# BaseMachine_Sequencer_UI.net
KiCad netlist of a schematic drawn in EAGLE
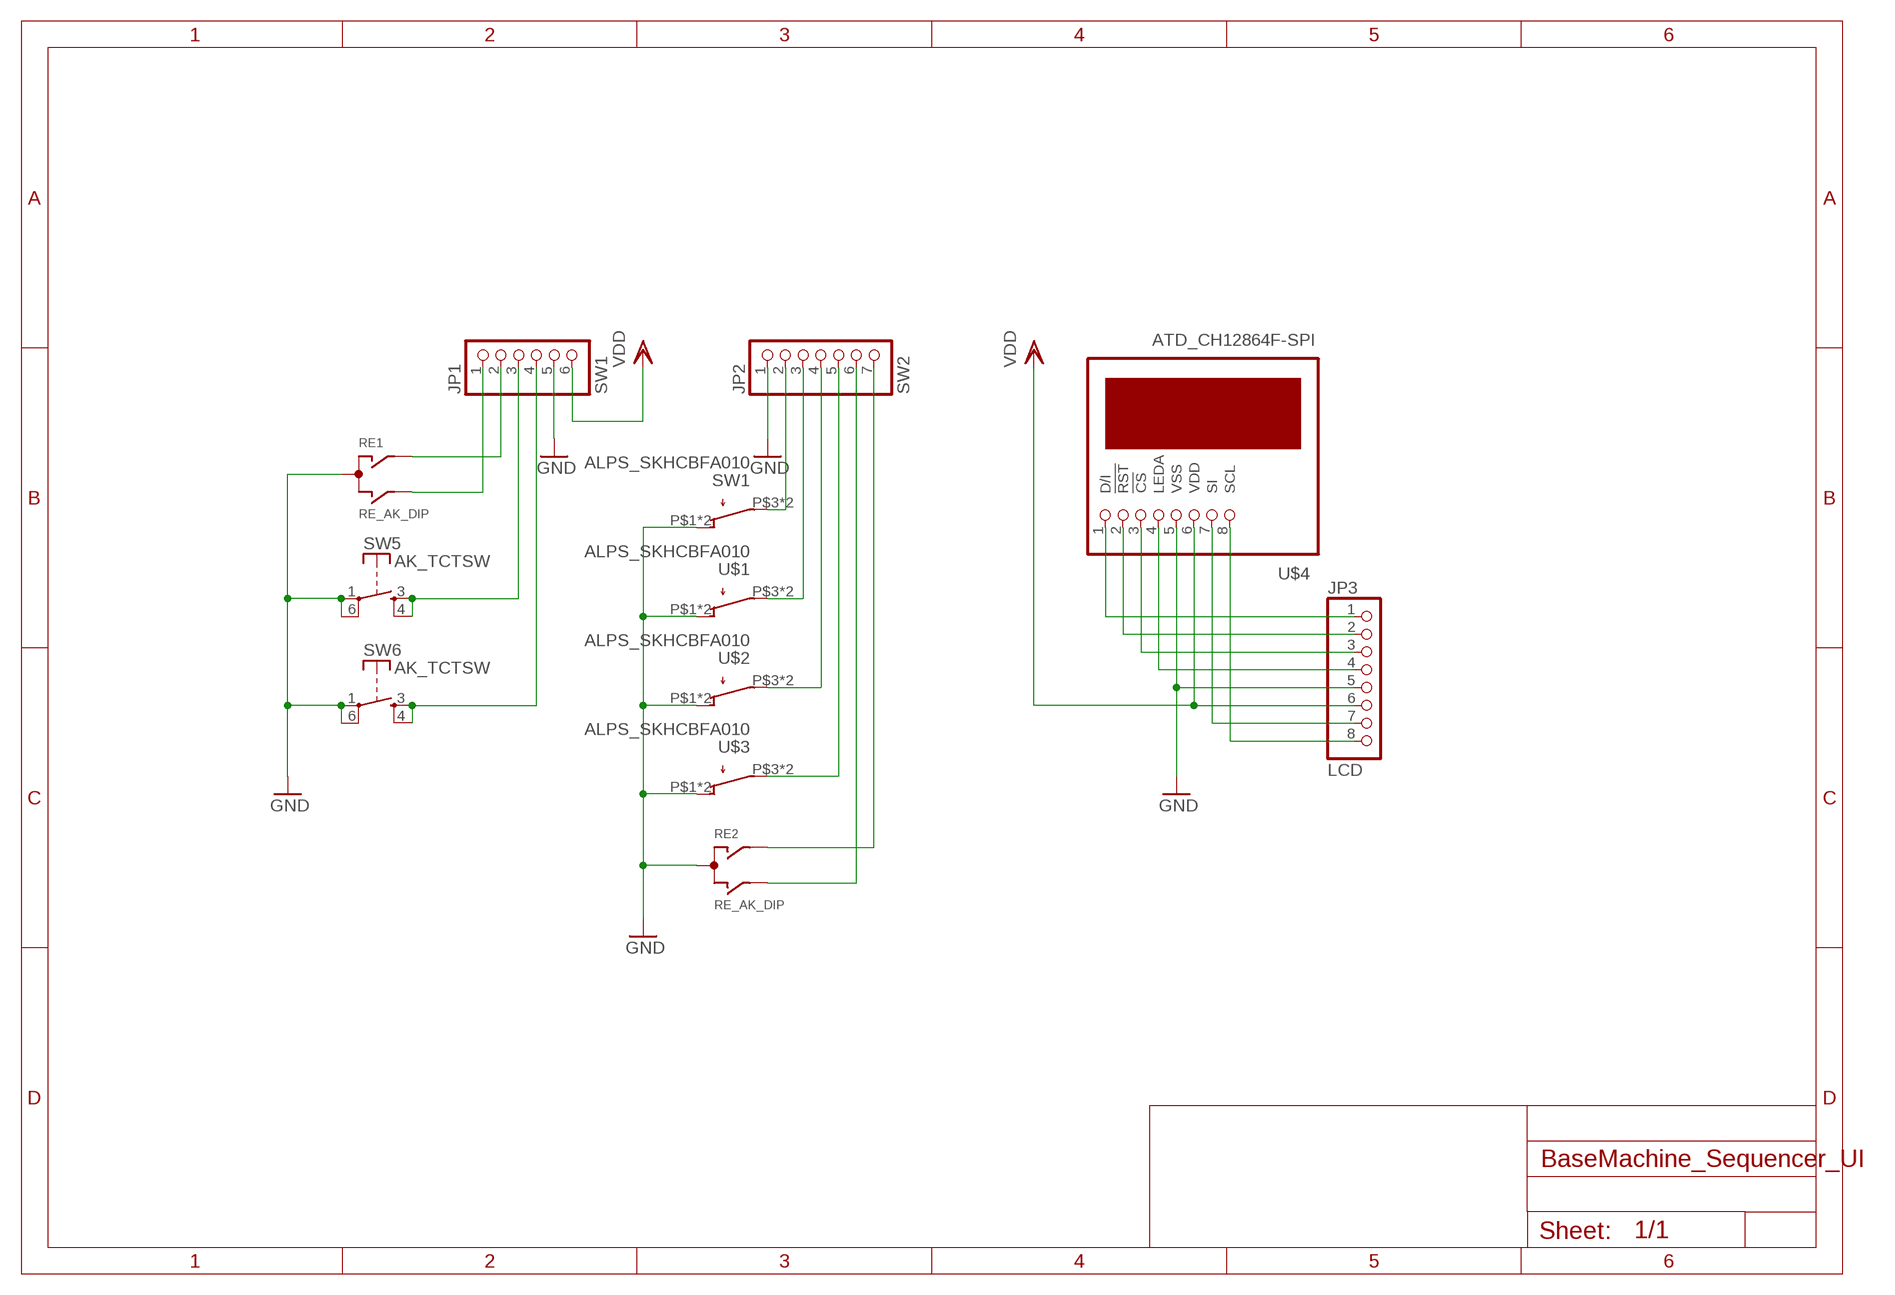
[diagram p0: schematic, sheet 1]

(export (version "E")
  (design (tool "Eeschema 10.0.6"))
  (components
    (comp (ref "JP1")
      (value "SW1")
      (footprint "eagle-import:1X06_90")
      (libsource (lib "eagle-import") (part "PINHD-1X6/90"))
    )
    (comp (ref "JP2")
      (value "SW2")
      (footprint "eagle-import:1X07_90")
      (libsource (lib "eagle-import") (part "PINHD-1X7/90"))
    )
    (comp (ref "JP3")
      (value "LCD")
      (footprint "eagle-import:1X08_90")
      (libsource (lib "eagle-import") (part "PINHD-1X8/90"))
    )
    (comp (ref "RE1")
      (value "RE_AK_DIP")
      (footprint "eagle-import:RE_AK_DIP")
      (libsource (lib "eagle-import") (part "RE_AK_DIP"))
    )
    (comp (ref "RE2")
      (value "RE_AK_DIP")
      (footprint "eagle-import:RE_AK_DIP")
      (libsource (lib "eagle-import") (part "RE_AK_DIP"))
    )
    (comp (ref "SW1")
      (value "ALPS_SKHCBFA010")
      (footprint "eagle-import:ALPS_SKHCBFA010")
      (libsource (lib "eagle-import") (part "ALPS_SKHCBFA010"))
    )
    (comp (ref "SW5")
      (value "AK_TCTSW")
      (footprint "eagle-import:TME1")
      (libsource (lib "eagle-import") (part "AK_TCTSW"))
    )
    (comp (ref "SW6")
      (value "AK_TCTSW")
      (footprint "eagle-import:TME1")
      (libsource (lib "eagle-import") (part "AK_TCTSW"))
    )
    (comp (ref "U$1")
      (value "ALPS_SKHCBFA010")
      (footprint "eagle-import:ALPS_SKHCBFA010")
      (libsource (lib "eagle-import") (part "ALPS_SKHCBFA010"))
    )
    (comp (ref "U$2")
      (value "ALPS_SKHCBFA010")
      (footprint "eagle-import:ALPS_SKHCBFA010")
      (libsource (lib "eagle-import") (part "ALPS_SKHCBFA010"))
    )
    (comp (ref "U$3")
      (value "ALPS_SKHCBFA010")
      (footprint "eagle-import:ALPS_SKHCBFA010")
      (libsource (lib "eagle-import") (part "ALPS_SKHCBFA010"))
    )
    (comp (ref "U$4")
      (value "ATD_CH12864F-SPI")
      (footprint "eagle-import:ATD-CH12864F-SPI")
      (libsource (lib "eagle-import") (part "ATD_CH12864F-SPI"))
    )
  )
  (nets
    (net (code "1") (name "GND") (class "Default")
      (node (ref "JP1") (pin "5") (pinfunction "5_5") (pintype "passive"))
      (node (ref "JP2") (pin "1") (pinfunction "1_1") (pintype "passive"))
      (node (ref "JP3") (pin "5") (pinfunction "5_5") (pintype "passive"))
      (node (ref "RE1") (pin "P$3") (pinfunction "C_P$3") (pintype "passive"))
      (node (ref "RE2") (pin "P$3") (pinfunction "C_P$3") (pintype "passive"))
      (node (ref "SW1") (pin "P$1") (pinfunction "O_P$1") (pintype "passive"))
      (node (ref "SW1") (pin "P$2") (pinfunction "O_P$2") (pintype "passive"))
      (node (ref "SW5") (pin "1") (pinfunction "P_1") (pintype "passive"))
      (node (ref "SW5") (pin "6") (pinfunction "P_6") (pintype "passive"))
      (node (ref "SW6") (pin "1") (pinfunction "P_1") (pintype "passive"))
      (node (ref "SW6") (pin "6") (pinfunction "P_6") (pintype "passive"))
      (node (ref "U$1") (pin "P$1") (pinfunction "O_P$1") (pintype "passive"))
      (node (ref "U$1") (pin "P$2") (pinfunction "O_P$2") (pintype "passive"))
      (node (ref "U$2") (pin "P$1") (pinfunction "O_P$1") (pintype "passive"))
      (node (ref "U$2") (pin "P$2") (pinfunction "O_P$2") (pintype "passive"))
      (node (ref "U$3") (pin "P$1") (pinfunction "O_P$1") (pintype "passive"))
      (node (ref "U$3") (pin "P$2") (pinfunction "O_P$2") (pintype "passive"))
      (node (ref "U$4") (pin "5") (pinfunction "VSS_5") (pintype "passive"))
    )
    (net (code "2") (name "Net-(JP1-Pad3)") (class "Default")
      (node (ref "JP1") (pin "3") (pinfunction "3_3") (pintype "passive"))
      (node (ref "SW5") (pin "3") (pinfunction "S_3") (pintype "passive"))
      (node (ref "SW5") (pin "4") (pinfunction "S_4") (pintype "passive"))
    )
    (net (code "3") (name "Net-(JP1-Pad4)") (class "Default")
      (node (ref "JP1") (pin "4") (pinfunction "4_4") (pintype "passive"))
      (node (ref "SW6") (pin "3") (pinfunction "S_3") (pintype "passive"))
      (node (ref "SW6") (pin "4") (pinfunction "S_4") (pintype "passive"))
    )
    (net (code "4") (name "Net-(JP2-Pad2)") (class "Default")
      (node (ref "JP2") (pin "2") (pinfunction "2_2") (pintype "passive"))
      (node (ref "SW1") (pin "P$3") (pinfunction "P_P$3") (pintype "passive"))
      (node (ref "SW1") (pin "P$4") (pinfunction "P_P$4") (pintype "passive"))
    )
    (net (code "5") (name "Net-(JP2-Pad3)") (class "Default")
      (node (ref "JP2") (pin "3") (pinfunction "3_3") (pintype "passive"))
      (node (ref "U$1") (pin "P$3") (pinfunction "P_P$3") (pintype "passive"))
      (node (ref "U$1") (pin "P$4") (pinfunction "P_P$4") (pintype "passive"))
    )
    (net (code "6") (name "Net-(JP2-Pad4)") (class "Default")
      (node (ref "JP2") (pin "4") (pinfunction "4_4") (pintype "passive"))
      (node (ref "U$2") (pin "P$3") (pinfunction "P_P$3") (pintype "passive"))
      (node (ref "U$2") (pin "P$4") (pinfunction "P_P$4") (pintype "passive"))
    )
    (net (code "7") (name "Net-(JP2-Pad5)") (class "Default")
      (node (ref "JP2") (pin "5") (pinfunction "5_5") (pintype "passive"))
      (node (ref "U$3") (pin "P$3") (pinfunction "P_P$3") (pintype "passive"))
      (node (ref "U$3") (pin "P$4") (pinfunction "P_P$4") (pintype "passive"))
    )
    (net (code "8") (name "Net-(RE1-A)") (class "Default")
      (node (ref "JP1") (pin "2") (pinfunction "2_2") (pintype "passive"))
      (node (ref "RE1") (pin "P$2") (pinfunction "A_P$2") (pintype "passive"))
    )
    (net (code "9") (name "Net-(RE1-B)") (class "Default")
      (node (ref "JP1") (pin "1") (pinfunction "1_1") (pintype "passive"))
      (node (ref "RE1") (pin "P$4") (pinfunction "B_P$4") (pintype "passive"))
    )
    (net (code "10") (name "Net-(RE2-A)") (class "Default")
      (node (ref "JP2") (pin "7") (pinfunction "7_7") (pintype "passive"))
      (node (ref "RE2") (pin "P$2") (pinfunction "A_P$2") (pintype "passive"))
    )
    (net (code "11") (name "Net-(RE2-B)") (class "Default")
      (node (ref "JP2") (pin "6") (pinfunction "6_6") (pintype "passive"))
      (node (ref "RE2") (pin "P$4") (pinfunction "B_P$4") (pintype "passive"))
    )
    (net (code "12") (name "Net-(U$4-D{slash}I)") (class "Default")
      (node (ref "JP3") (pin "1") (pinfunction "1_1") (pintype "passive"))
      (node (ref "U$4") (pin "1") (pinfunction "D/I_1") (pintype "passive"))
    )
    (net (code "13") (name "Net-(U$4-LEDA)") (class "Default")
      (node (ref "JP3") (pin "4") (pinfunction "4_4") (pintype "passive"))
      (node (ref "U$4") (pin "4") (pinfunction "LEDA_4") (pintype "passive"))
    )
    (net (code "14") (name "Net-(U$4-SCL)") (class "Default")
      (node (ref "JP3") (pin "8") (pinfunction "8_8") (pintype "passive"))
      (node (ref "U$4") (pin "8") (pinfunction "SCL_8") (pintype "passive"))
    )
    (net (code "15") (name "Net-(U$4-SI)") (class "Default")
      (node (ref "JP3") (pin "7") (pinfunction "7_7") (pintype "passive"))
      (node (ref "U$4") (pin "7") (pinfunction "SI_7") (pintype "passive"))
    )
    (net (code "16") (name "Net-(U$4-~{CS})") (class "Default")
      (node (ref "JP3") (pin "3") (pinfunction "3_3") (pintype "passive"))
      (node (ref "U$4") (pin "3") (pinfunction "~{CS}_3") (pintype "passive"))
    )
    (net (code "17") (name "Net-(U$4-~{RST})") (class "Default")
      (node (ref "JP3") (pin "2") (pinfunction "2_2") (pintype "passive"))
      (node (ref "U$4") (pin "2") (pinfunction "~{RST}_2") (pintype "passive"))
    )
    (net (code "18") (name "VDD") (class "Default")
      (node (ref "JP1") (pin "6") (pinfunction "6_6") (pintype "passive"))
      (node (ref "JP3") (pin "6") (pinfunction "6_6") (pintype "passive"))
      (node (ref "U$4") (pin "6") (pinfunction "VDD_6") (pintype "passive"))
    )
  )
)
